# IMD_AMS_Latch.net
KiCad netlist of a schematic drawn in EAGLE
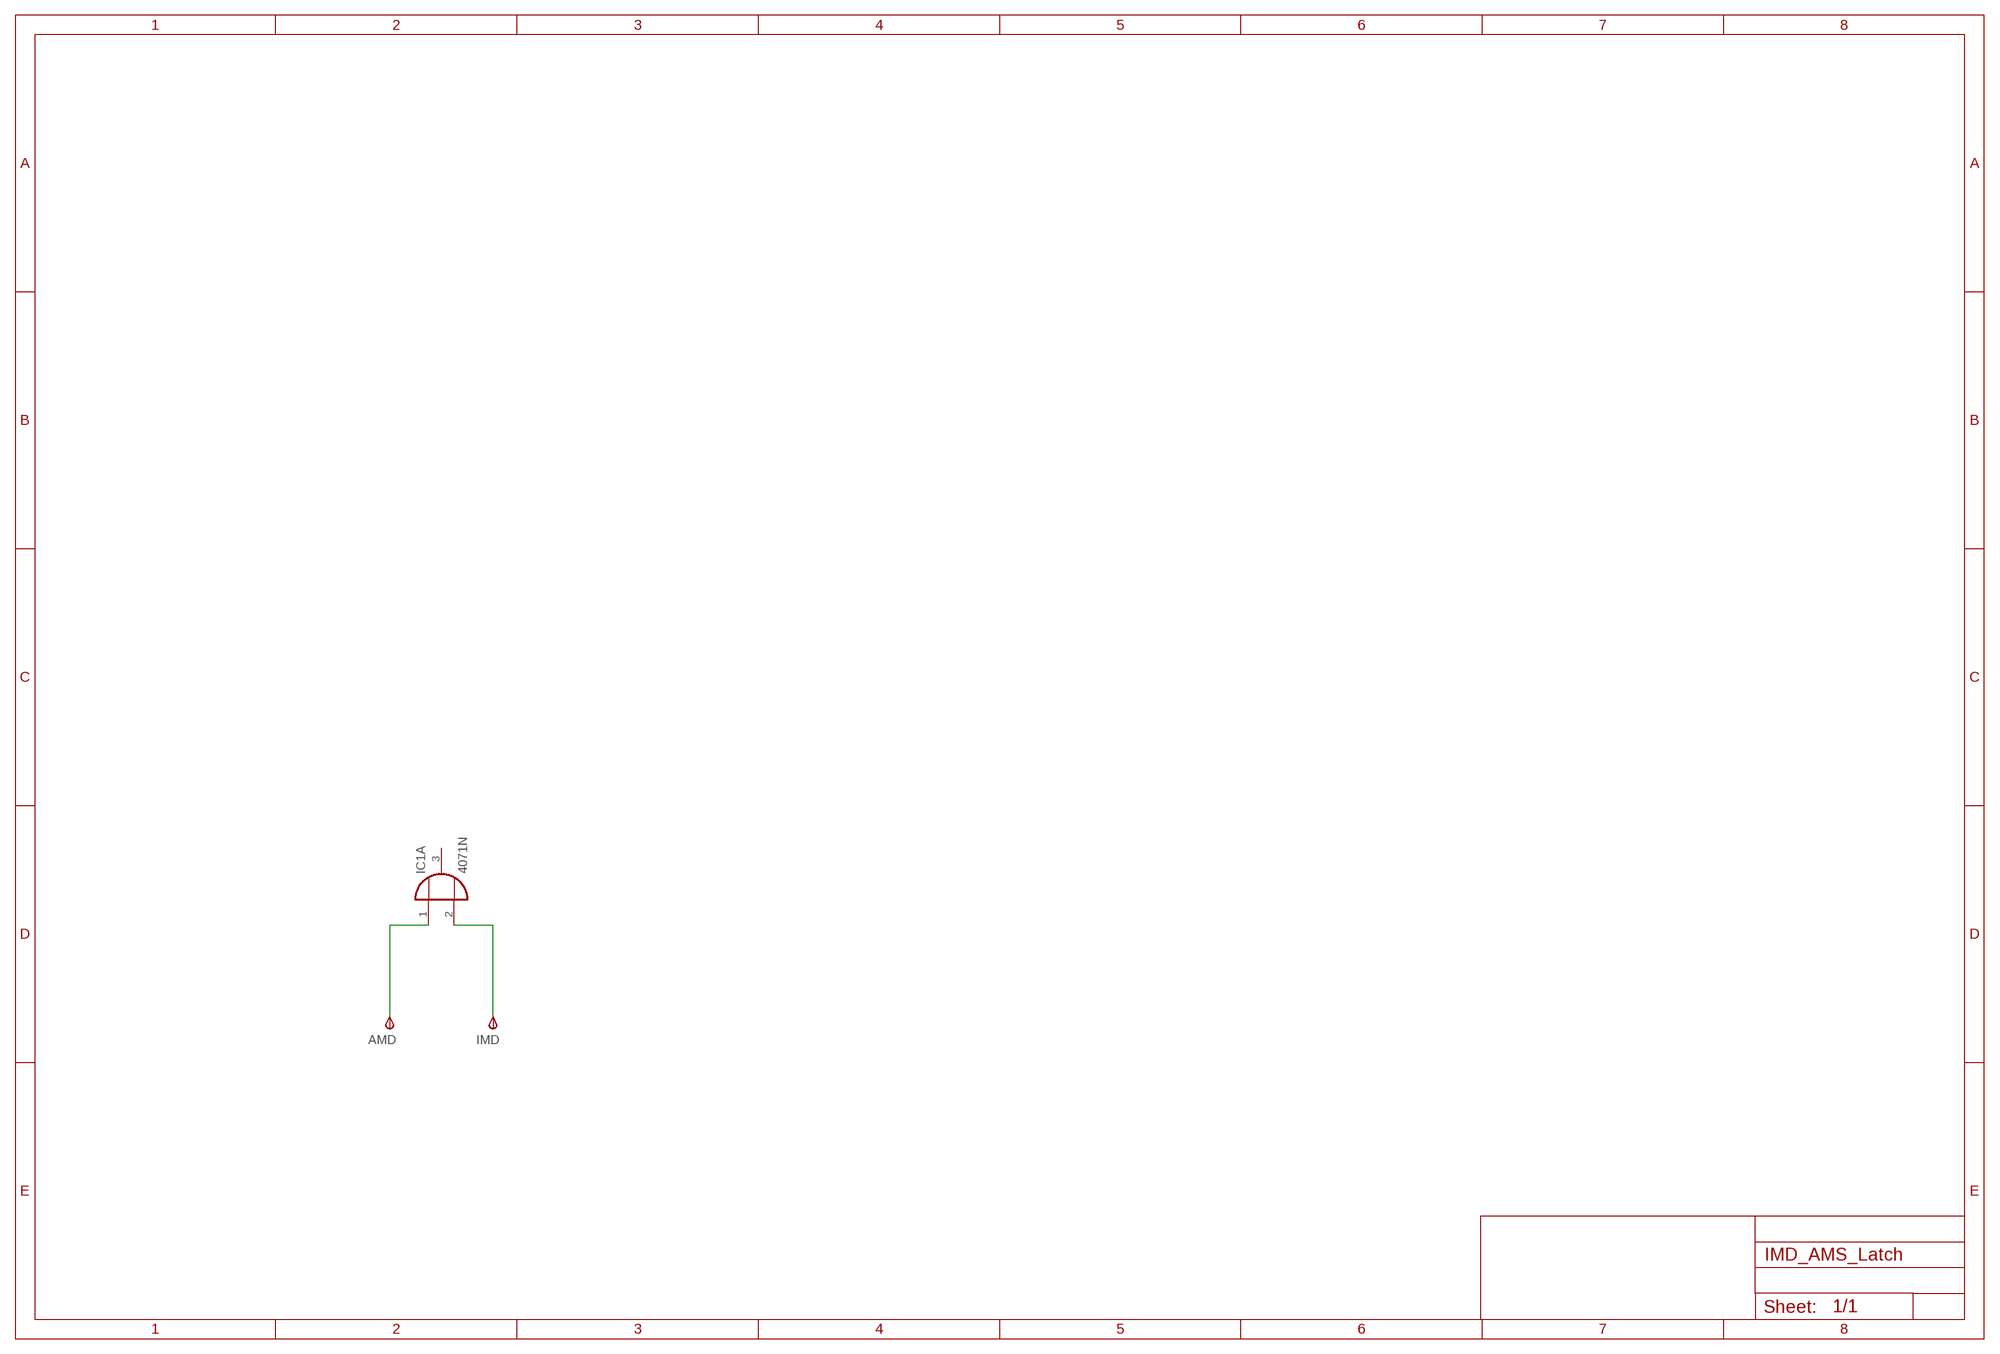
[diagram p0: schematic, sheet 1]

(export (version "E")
  (design (tool "Eeschema 10.0.6"))
  (components
    (comp (ref "AMD")
      (value "TPSPAD1-13")
      (footprint "eagle-import:P1-13")
      (libsource (lib "eagle-import") (part "TPSPAD1-13"))
    )
    (comp (ref "IC1")
      (value "4071N")
      (footprint "eagle-import:DIL14")
      (libsource (lib "eagle-import") (part "4071N"))
    )
    (comp (ref "IMD")
      (value "TPSPAD1-13")
      (footprint "eagle-import:P1-13")
      (libsource (lib "eagle-import") (part "TPSPAD1-13"))
    )
  )
  (nets
    (net (code "1") (name "Net-(AMD-PP)") (class "Default")
      (node (ref "AMD") (pin "TP") (pinfunction "PP_TP") (pintype "input"))
      (node (ref "IC1") (pin "1") (pinfunction "I0_1") (pintype "input"))
    )
    (net (code "2") (name "Net-(IC1A-I1)") (class "Default")
      (node (ref "IC1") (pin "2") (pinfunction "I1_2") (pintype "input"))
      (node (ref "IMD") (pin "TP") (pinfunction "PP_TP") (pintype "input"))
    )
    (net (code "3") (name "unconnected-(IC1A-O-Pad3)") (class "Default")
      (node (ref "IC1") (pin "3") (pinfunction "O_3") (pintype "output"))
    )
  )
)
